# main.net
KiCad netlist of a schematic drawn in EAGLE
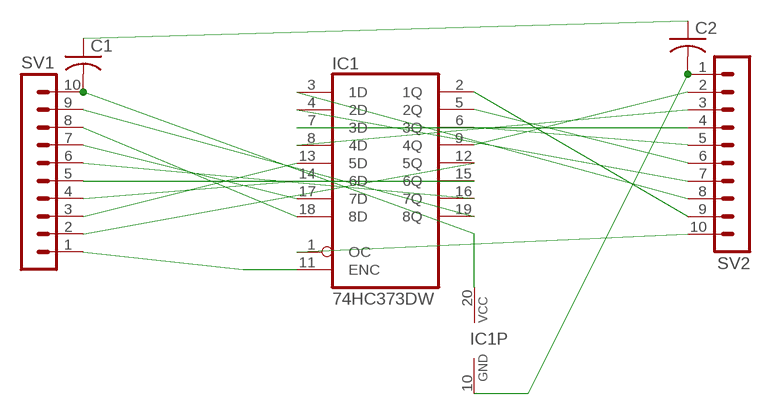
[diagram p0: schematic, sheet 1]

(export (version "E")
  (design (tool "Eeschema 10.0.6"))
  (components
    (comp (ref "C1")
      (value "C-USC0603")
      (footprint "eagle-import:C0603")
      (libsource (lib "eagle-import") (part "C-USC0603"))
    )
    (comp (ref "C2")
      (value "C-USC0603")
      (footprint "eagle-import:C0603")
      (libsource (lib "eagle-import") (part "C-USC0603"))
    )
    (comp (ref "IC1")
      (value "74HC373DW")
      (footprint "eagle-import:SO20W")
      (libsource (lib "eagle-import") (part "74373DWHC"))
    )
    (comp (ref "SV1")
      (value "MA10-1")
      (footprint "eagle-import:MA10-1")
      (libsource (lib "eagle-import") (part "MA10-1"))
    )
    (comp (ref "SV2")
      (value "MA10-1")
      (footprint "eagle-import:MA10-1")
      (libsource (lib "eagle-import") (part "MA10-1"))
    )
  )
  (nets
    (net (code "1") (name "Net-(C1-Pad1)") (class "Default")
      (node (ref "C1") (pin "1") (pinfunction "1_1") (pintype "passive"))
      (node (ref "C2") (pin "1") (pinfunction "1_1") (pintype "passive"))
    )
    (net (code "2") (name "Net-(IC1A-1D)") (class "Default")
      (node (ref "IC1") (pin "3") (pinfunction "1D_3") (pintype "input"))
      (node (ref "SV2") (pin "8") (pinfunction "8_8") (pintype "passive"))
    )
    (net (code "3") (name "Net-(IC1A-1Q)") (class "Default")
      (node (ref "IC1") (pin "2") (pinfunction "1Q_2") (pintype "tri_state"))
      (node (ref "SV2") (pin "9") (pinfunction "9_9") (pintype "passive"))
    )
    (net (code "4") (name "Net-(IC1A-2D)") (class "Default")
      (node (ref "IC1") (pin "4") (pinfunction "2D_4") (pintype "input"))
      (node (ref "SV2") (pin "7") (pinfunction "7_7") (pintype "passive"))
    )
    (net (code "5") (name "Net-(IC1A-2Q)") (class "Default")
      (node (ref "IC1") (pin "5") (pinfunction "2Q_5") (pintype "tri_state"))
      (node (ref "SV2") (pin "6") (pinfunction "6_6") (pintype "passive"))
    )
    (net (code "6") (name "Net-(IC1A-3D)") (class "Default")
      (node (ref "IC1") (pin "7") (pinfunction "3D_7") (pintype "input"))
      (node (ref "SV2") (pin "4") (pinfunction "4_4") (pintype "passive"))
    )
    (net (code "7") (name "Net-(IC1A-3Q)") (class "Default")
      (node (ref "IC1") (pin "6") (pinfunction "3Q_6") (pintype "tri_state"))
      (node (ref "SV2") (pin "5") (pinfunction "5_5") (pintype "passive"))
    )
    (net (code "8") (name "Net-(IC1A-4D)") (class "Default")
      (node (ref "IC1") (pin "8") (pinfunction "4D_8") (pintype "input"))
      (node (ref "SV2") (pin "3") (pinfunction "3_3") (pintype "passive"))
    )
    (net (code "9") (name "Net-(IC1A-4Q)") (class "Default")
      (node (ref "IC1") (pin "9") (pinfunction "4Q_9") (pintype "tri_state"))
      (node (ref "SV2") (pin "2") (pinfunction "2_2") (pintype "passive"))
    )
    (net (code "10") (name "Net-(IC1A-5D)") (class "Default")
      (node (ref "IC1") (pin "13") (pinfunction "5D_13") (pintype "input"))
      (node (ref "SV1") (pin "3") (pinfunction "3_3") (pintype "passive"))
    )
    (net (code "11") (name "Net-(IC1A-5Q)") (class "Default")
      (node (ref "IC1") (pin "12") (pinfunction "5Q_12") (pintype "tri_state"))
      (node (ref "SV1") (pin "2") (pinfunction "2_2") (pintype "passive"))
    )
    (net (code "12") (name "Net-(IC1A-6D)") (class "Default")
      (node (ref "IC1") (pin "14") (pinfunction "6D_14") (pintype "input"))
      (node (ref "SV1") (pin "4") (pinfunction "4_4") (pintype "passive"))
    )
    (net (code "13") (name "Net-(IC1A-6Q)") (class "Default")
      (node (ref "IC1") (pin "15") (pinfunction "6Q_15") (pintype "tri_state"))
      (node (ref "SV1") (pin "5") (pinfunction "5_5") (pintype "passive"))
    )
    (net (code "14") (name "Net-(IC1A-7D)") (class "Default")
      (node (ref "IC1") (pin "17") (pinfunction "7D_17") (pintype "input"))
      (node (ref "SV1") (pin "7") (pinfunction "7_7") (pintype "passive"))
    )
    (net (code "15") (name "Net-(IC1A-7Q)") (class "Default")
      (node (ref "IC1") (pin "16") (pinfunction "7Q_16") (pintype "tri_state"))
      (node (ref "SV1") (pin "6") (pinfunction "6_6") (pintype "passive"))
    )
    (net (code "16") (name "Net-(IC1A-8D)") (class "Default")
      (node (ref "IC1") (pin "18") (pinfunction "8D_18") (pintype "input"))
      (node (ref "SV1") (pin "8") (pinfunction "8_8") (pintype "passive"))
    )
    (net (code "17") (name "Net-(IC1A-8Q)") (class "Default")
      (node (ref "IC1") (pin "19") (pinfunction "8Q_19") (pintype "tri_state"))
      (node (ref "SV1") (pin "9") (pinfunction "9_9") (pintype "passive"))
    )
    (net (code "18") (name "Net-(IC1A-ENC)") (class "Default")
      (node (ref "IC1") (pin "11") (pinfunction "ENC_11") (pintype "input"))
      (node (ref "SV1") (pin "1") (pinfunction "1_1") (pintype "passive"))
    )
    (net (code "19") (name "Net-(IC1A-OC)") (class "Default")
      (node (ref "IC1") (pin "1") (pinfunction "OC_1") (pintype "input"))
      (node (ref "SV2") (pin "10") (pinfunction "10_10") (pintype "passive"))
    )
    (net (code "20") (name "Net-(IC1B-GND)") (class "Default")
      (node (ref "C2") (pin "2") (pinfunction "2_2") (pintype "passive"))
      (node (ref "IC1") (pin "10") (pinfunction "GND_10") (pintype "power_in"))
      (node (ref "SV2") (pin "1") (pinfunction "1_1") (pintype "passive"))
    )
    (net (code "21") (name "Net-(IC1B-VCC)") (class "Default")
      (node (ref "C1") (pin "2") (pinfunction "2_2") (pintype "passive"))
      (node (ref "IC1") (pin "20") (pinfunction "VCC_20") (pintype "power_in"))
      (node (ref "SV1") (pin "10") (pinfunction "10_10") (pintype "passive"))
    )
  )
)
